# easyeda.net
KiCad netlist of a schematic drawn in EasyEDA
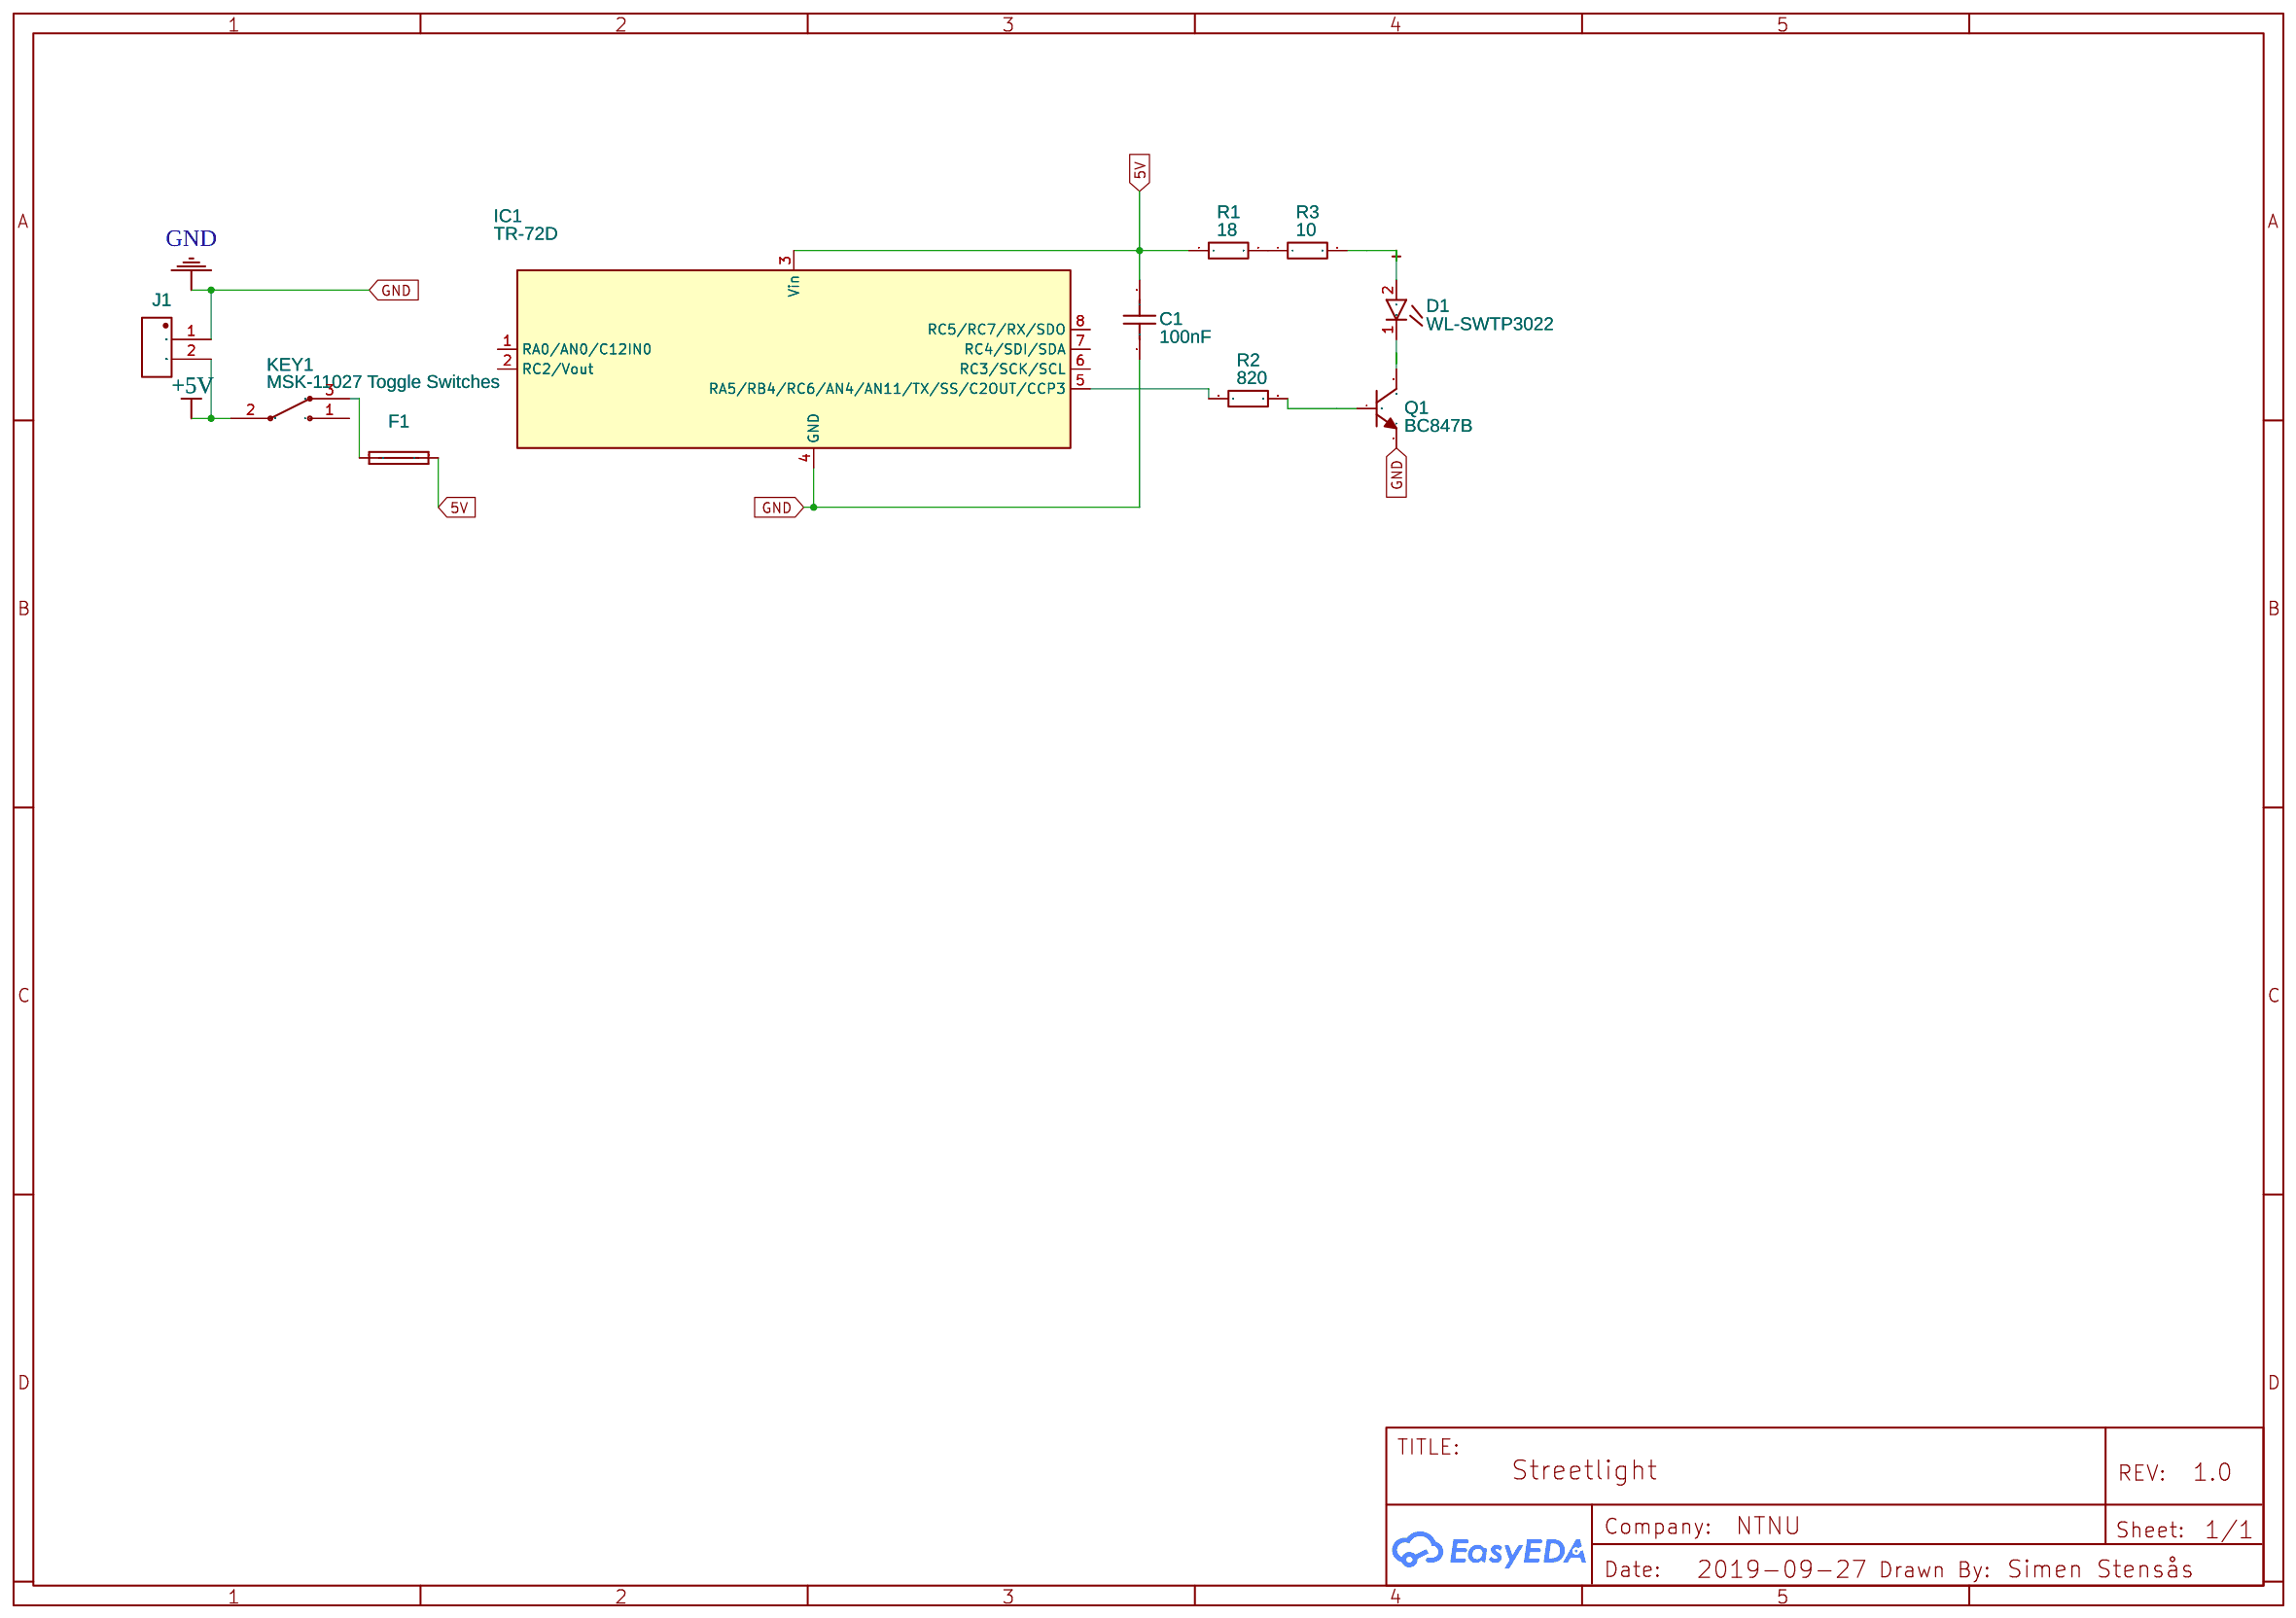
[diagram p0: schematic sheet]

(export (version "E")
  (design (tool "Eeschema 10.0.6"))
  (components
    (comp (ref "C1")
      (value "100nF")
      (fields
        (field (name "BOM_Manufacturer Part") "1210B106K100CT")
        (field (name "BOM_Supplier Part") "C304011")
      )
      (libsource (lib "") (part "1210B106K100CT"))
    )
    (comp (ref "D1") (value "WL-SWTP3022") (libsource (lib "") (part "Unknown_715_135")))
    (comp (ref "F1")
      (value "NO")
      (fields
        (field (name "BOM_Manufacturer Part") "3403.0015.11")
        (field (name "BOM_Supplier Part") "693-3403.0015.11")
      )
      (libsource (lib "") (part "Unknown_200_215"))
    )
    (comp (ref "IC1") (value "TR-72D") (libsource (lib "") (part "Unknown_255_170")))
    (comp (ref "J1")
      (value "KF127_2P_5.08")
      (fields (field (name "BOM_Manufacturer Part") "KF127L-5.08"))
      (libsource (lib "") (part "Unknown_85_170"))
    )
    (comp (ref "KEY1")
      (value "MSK-11027 Toggle Switches")
      (fields (field (name "BOM_Supplier Part") "C21381"))
      (libsource (lib "") (part "Unknown_140_195"))
    )
    (comp (ref "Q1")
      (value "BC847B")
      (fields (field (name "BOM_Supplier Part") "C181140"))
      (libsource (lib "") (part "Unknown_690_200"))
    )
    (comp (ref "R1")
      (value "18")
      (fields
        (field (name "BOM_Manufacturer Part") "CR1206-FX-18R0ELF")
        (field (name "BOM_Supplier Part") "C204720")
      )
      (libsource (lib "") (part "CR1206-FX-18R0ELF"))
    )
    (comp (ref "R2")
      (value "820")
      (fields
        (field (name "BOM_Manufacturer Part") "AECR1206F820RK9")
        (field (name "BOM_Supplier Part") "C352031")
      )
      (libsource (lib "") (part "AECR1206F820RK9"))
    )
    (comp (ref "R3")
      (value "10")
      (fields
        (field (name "BOM_Manufacturer Part") "AECR1206F10R0K9")
        (field (name "BOM_Supplier Part") "C352161")
      )
      (libsource (lib "") (part "AECR1206F10R0K9"))
    )
  )
  (nets
    (net (code "1") (name "+5V") (class "Default")
      (node (ref "J1") (pin "2") (pinfunction "PIN2_2") (pintype "unspecified"))
      (node (ref "KEY1") (pin "2") (pinfunction "2_2") (pintype "unspecified"))
    )
    (net (code "2") (name "5V") (class "Default")
      (node (ref "C1") (pin "2") (pinfunction "2_2") (pintype "unspecified"))
      (node (ref "F1") (pin "2") (pinfunction "2_2") (pintype "bidirectional"))
      (node (ref "IC1") (pin "3") (pinfunction "Vin_3") (pintype "bidirectional"))
      (node (ref "R1") (pin "1") (pinfunction "1_1") (pintype "unspecified"))
    )
    (net (code "3") (name "GND") (class "Default")
      (node (ref "C1") (pin "1") (pinfunction "1_1") (pintype "unspecified"))
      (node (ref "IC1") (pin "4") (pinfunction "GND_4") (pintype "bidirectional"))
      (node (ref "J1") (pin "1") (pinfunction "PIN1_1") (pintype "unspecified"))
      (node (ref "Q1") (pin "2") (pinfunction "E_2") (pintype "input"))
    )
    (net (code "4") (name "Net-(D1-Pad2)") (class "Default")
      (node (ref "D1") (pin "2") (pinfunction "2_2") (pintype "unspecified"))
      (node (ref "R3") (pin "2") (pinfunction "2_2") (pintype "unspecified"))
    )
    (net (code "5") (name "Net-(F1-Pad1)") (class "Default")
      (node (ref "F1") (pin "1") (pinfunction "1_1") (pintype "bidirectional"))
      (node (ref "KEY1") (pin "3") (pinfunction "3_3") (pintype "unspecified"))
    )
    (net (code "6") (name "Net-(IC1-RA5{slash}RB4{slash}RC6{slash}AN4{slash}AN11{slash}TX{slash}SS{slash}C2OUT{slash}CCP3)") (class "Default")
      (node (ref "IC1") (pin "5") (pinfunction "RA5/RB4/RC6/AN4/AN11/TX/SS/C2OUT/CCP3_5") (pintype "bidirectional"))
      (node (ref "R2") (pin "1") (pinfunction "1_1") (pintype "unspecified"))
    )
    (net (code "7") (name "Net-(Q1-B)") (class "Default")
      (node (ref "Q1") (pin "1") (pinfunction "B_1") (pintype "input"))
      (node (ref "R2") (pin "2") (pinfunction "2_2") (pintype "unspecified"))
    )
    (net (code "8") (name "Net-(Q1-C)") (class "Default")
      (node (ref "D1") (pin "1") (pinfunction "1_1") (pintype "unspecified"))
      (node (ref "Q1") (pin "3") (pinfunction "C_3") (pintype "input"))
    )
    (net (code "9") (name "Net-(R1-Pad2)") (class "Default")
      (node (ref "R1") (pin "2") (pinfunction "2_2") (pintype "unspecified"))
      (node (ref "R3") (pin "1") (pinfunction "1_1") (pintype "unspecified"))
    )
    (net (code "10") (name "unconnected-(IC1-RA0{slash}AN0{slash}C12IN0-Pad1)") (class "Default")
      (node (ref "IC1") (pin "1") (pinfunction "RA0/AN0/C12IN0_1") (pintype "bidirectional"))
    )
    (net (code "11") (name "unconnected-(IC1-RC2{slash}Vout-Pad2)") (class "Default")
      (node (ref "IC1") (pin "2") (pinfunction "RC2/Vout_2") (pintype "bidirectional"))
    )
    (net (code "12") (name "unconnected-(IC1-RC3{slash}SCK{slash}SCL-Pad6)") (class "Default")
      (node (ref "IC1") (pin "6") (pinfunction "RC3/SCK/SCL_6") (pintype "bidirectional"))
    )
    (net (code "13") (name "unconnected-(IC1-RC4{slash}SDI{slash}SDA-Pad7)") (class "Default")
      (node (ref "IC1") (pin "7") (pinfunction "RC4/SDI/SDA_7") (pintype "bidirectional"))
    )
    (net (code "14") (name "unconnected-(IC1-RC5{slash}RC7{slash}RX{slash}SDO-Pad8)") (class "Default")
      (node (ref "IC1") (pin "8") (pinfunction "RC5/RC7/RX/SDO_8") (pintype "bidirectional"))
    )
    (net (code "15") (name "unconnected-(KEY1-Pad1)") (class "Default")
      (node (ref "KEY1") (pin "1") (pinfunction "1_1") (pintype "unspecified"))
    )
  )
)
